# A3000_8MB_Glue.net
KiCad netlist of a schematic drawn in Altium Designer
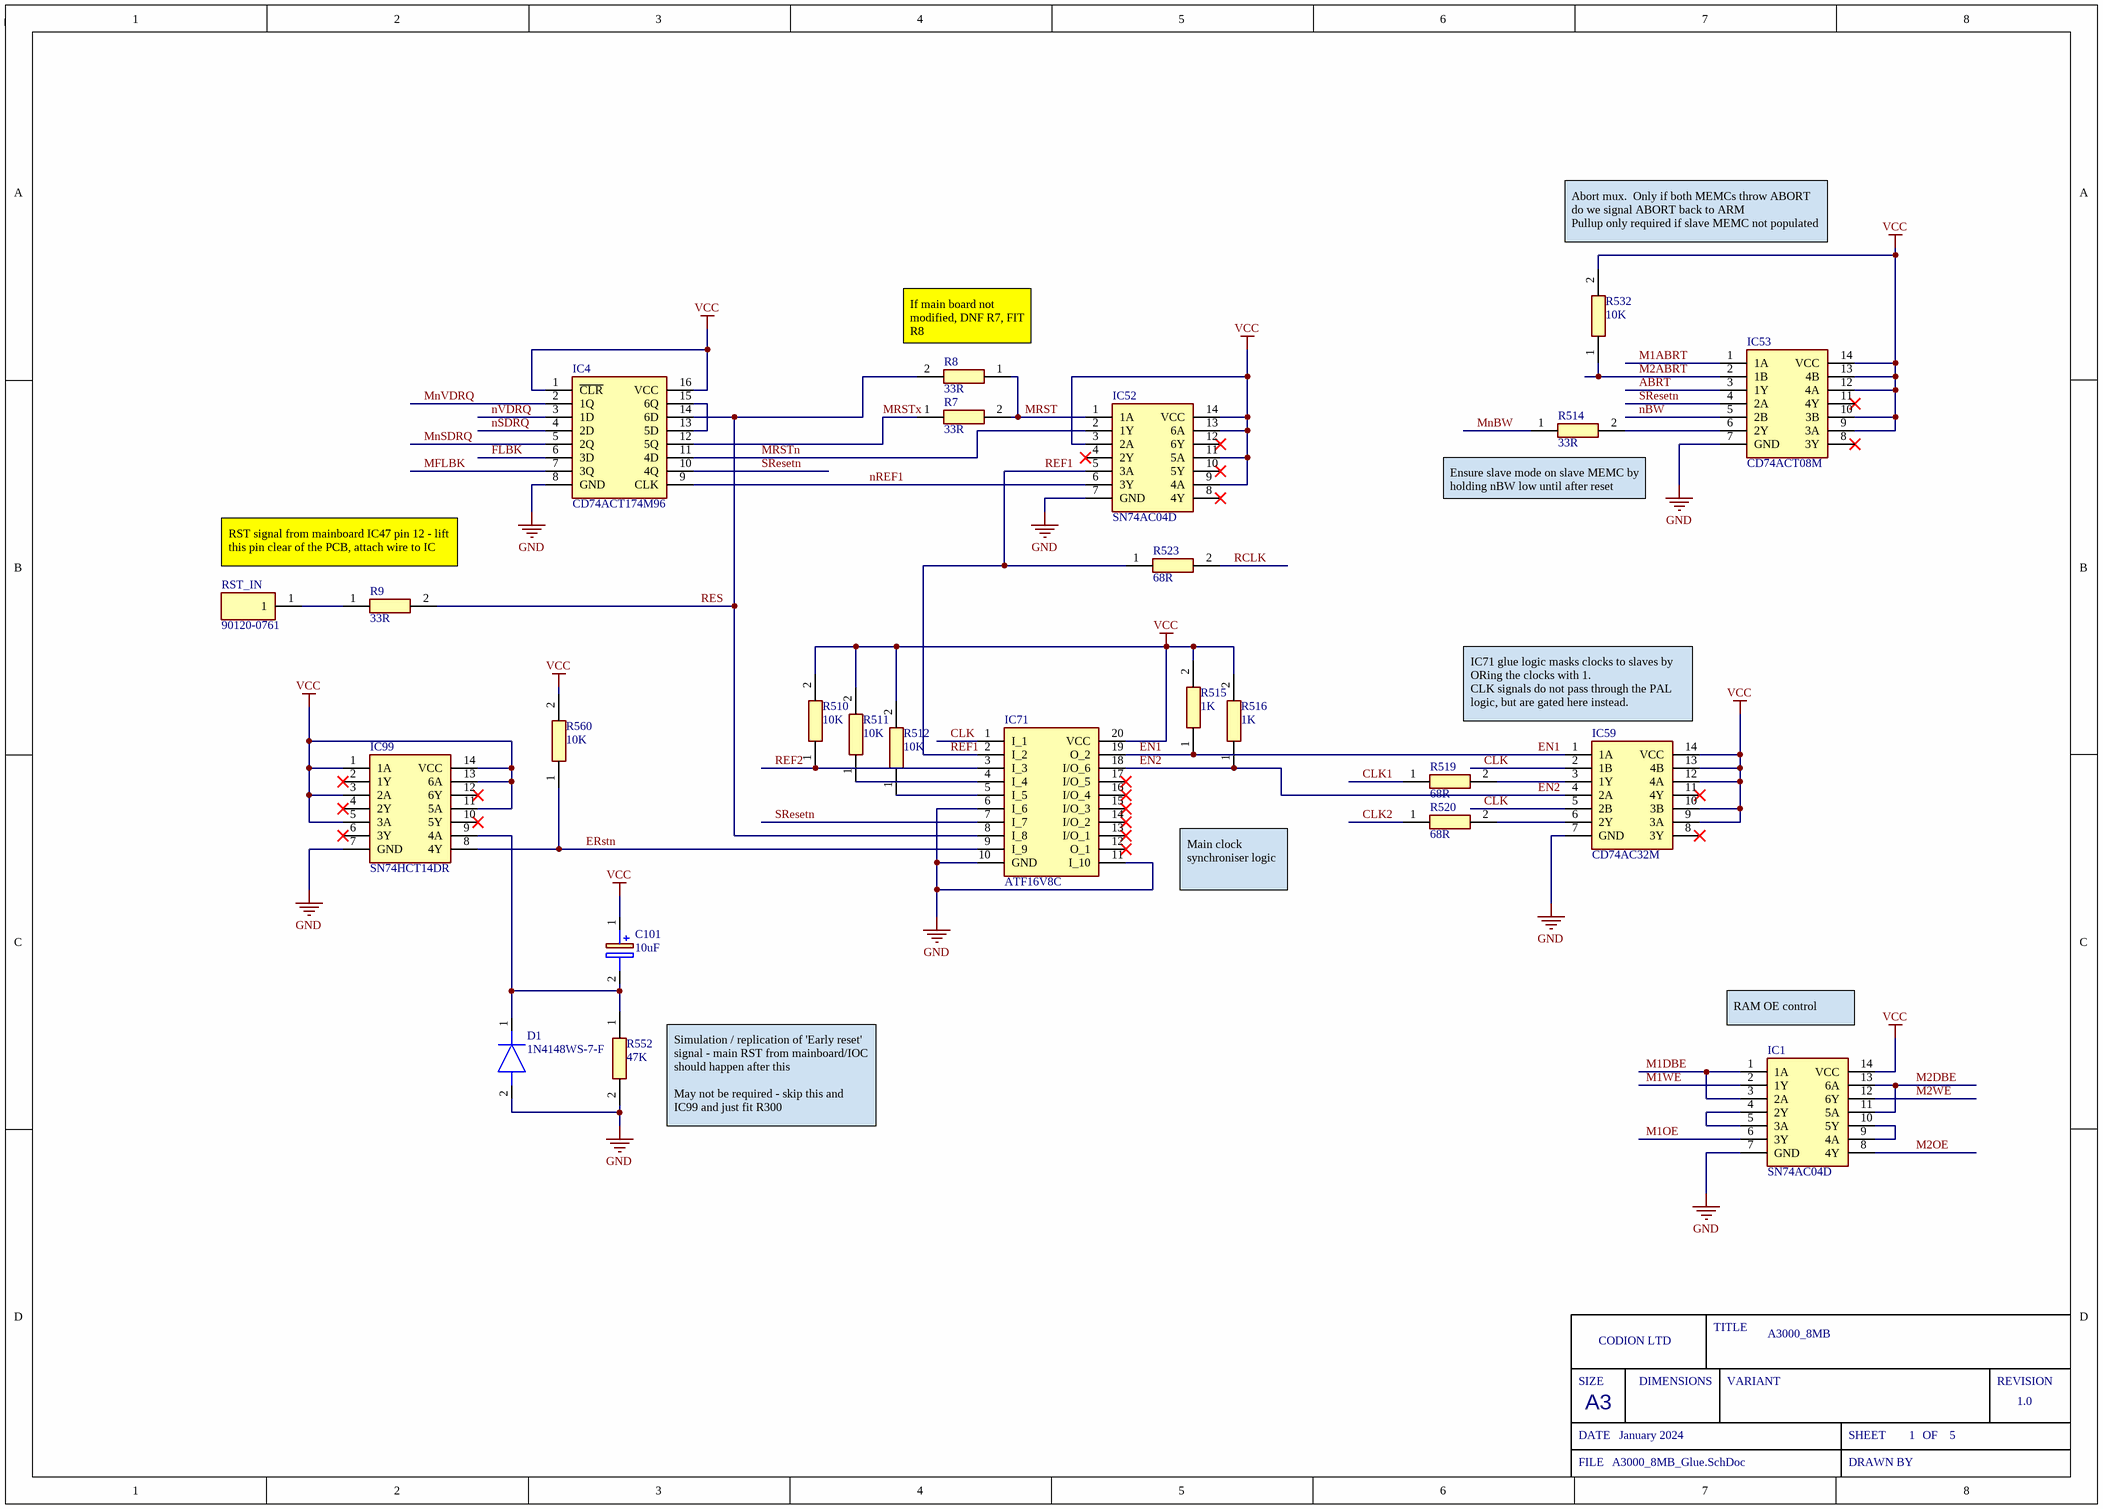
[diagram p0: A3000_8MB_Glue.SchDoc]

(export (version "E")
  (design (tool "Eeschema 10.0.6"))
  (components
    (comp (ref "C101")
      (value "10uF")
      (footprint "SamacSys:EEE0GA101SR")
      (description "Capacitor Polarised")
      (fields
        (field (name "MANUFACTURER_PART_NUMBER") "EEE-1EA100SR")
        (field (name "MOUSER PART NUMBER") "667-EEE-1EA100SR")
      )
      (libsource (lib "*") (part "EEE-1EA100SR"))
    )
    (comp (ref "D1")
      (value "1N4148WS-7-F")
      (footprint "SamacSys:SOD2513X120N")
      (description "Diode")
      (fields (field (name "MOUSER PART NUMBER") "621-1N4148WS-F") (field (name "LCSC PART #") "C2128"))
      (libsource (lib "SamacSys") (part "1N4148WS-7-F"))
    )
    (comp (ref "IC1")
      (value "SN74AC04D")
      (footprint "SamacSys:SOIC127P600X175-14N")
      (description "Integrated Circuit")
      (fields (field (name "MOUSER PART NUMBER") "595-SN74AC04D") (field (name "LCSC PART #") "C352940"))
      (libsource (lib "SamacSys") (part "SN74AC04D"))
    )
    (comp (ref "IC4")
      (value "CD74ACT174M96")
      (footprint "SamacSys:SOIC127P600X175-16N")
      (description "Integrated Circuit")
      (fields (field (name "MOUSER PART NUMBER") "595-CD74ACT174M96"))
      (libsource (lib "*") (part "CD74ACT174M96"))
    )
    (comp (ref "IC52")
      (value "SN74AC04D")
      (footprint "SamacSys:SOIC127P600X175-14N")
      (description "Integrated Circuit")
      (fields (field (name "MOUSER PART NUMBER") "595-SN74AC04D") (field (name "LCSC PART #") "C352940"))
      (libsource (lib "SamacSys") (part "SN74AC04D"))
    )
    (comp (ref "IC53")
      (value "CD74ACT08M")
      (footprint "SamacSys:SOIC127P600X175-14N")
      (description "Integrated Circuit")
      (fields (field (name "MOUSER PART NUMBER") "595-CD74ACT08M") (field (name "LCSC PART #") "C233452"))
      (libsource (lib "*") (part "CD74ACT08M"))
    )
    (comp (ref "IC59")
      (value "CD74AC32M")
      (footprint "SamacSys:SOIC127P600X175-14N")
      (description "Integrated Circuit")
      (fields (field (name "MOUSER PART NUMBER") "595-CD74AC32M") (field (name "LCSC PART #") "C352943"))
      (libsource (lib "SamacSys") (part "CD74AC32M"))
    )
    (comp (ref "IC71")
      (value "ATF16V8C")
      (footprint "SamacSys:DIP762W66P254L2692H508Q20N")
      (description "Integrated Circuit")
      (fields
        (field (name "MANUFACTURER_PART_NUMBER") "PAL16R4AMJ")
        (field (name "MOUSER PART NUMBER") "595-PAL16R4AMJ")
      )
      (libsource (lib "*") (part "PAL16R4AMJ"))
    )
    (comp (ref "IC99")
      (value "SN74HCT14DR")
      (footprint "SamacSys:SOIC127P600X175-14N")
      (description "Integrated Circuit")
      (fields (field (name "MOUSER PART NUMBER") "595-SN74HCT14DR") (field (name "LCSC PART #") "C6769"))
      (libsource (lib "SamacSys") (part "SN74HCT14DR"))
    )
    (comp (ref "R7")
      (value "33R")
      (footprint "SamacSys:RESC1005X40N")
      (description "Resistor")
      (fields
        (field (name "MANUFACTURER_PART_NUMBER") "CRCW040233R0FKED")
        (field (name "MOUSER PART NUMBER") "71-CRCW0402-33-E3")
      )
      (libsource (lib "SamacSys") (part "CRCW040233R0FKED"))
    )
    (comp (ref "R8")
      (value "33R")
      (footprint "SamacSys:RESC1005X40N")
      (description "Resistor")
      (fields
        (field (name "MANUFACTURER_PART_NUMBER") "CRCW040233R0FKED")
        (field (name "MOUSER PART NUMBER") "71-CRCW0402-33-E3")
      )
      (libsource (lib "") (part "CRCW040233R0FKED_1"))
    )
    (comp (ref "R9")
      (value "33R")
      (footprint "SamacSys:RESC1005X40N")
      (description "Resistor")
      (fields
        (field (name "MANUFACTURER_PART_NUMBER") "CRCW040233R0FKED")
        (field (name "MOUSER PART NUMBER") "71-CRCW0402-33-E3")
      )
      (libsource (lib "SamacSys") (part "CRCW040233R0FKED"))
    )
    (comp (ref "R510")
      (value "10K")
      (footprint "SamacSys:RESC1005X40N")
      (description "Resistor")
      (fields
        (field (name "MANUFACTURER_PART_NUMBER") "CRCW040210K0FKEDHP")
        (field (name "MOUSER PART NUMBER") "71-CRCW040210K0FKEDH")
      )
      (libsource (lib "SamacSys") (part "CRCW040210K0FKEDHP"))
    )
    (comp (ref "R511")
      (value "10K")
      (footprint "SamacSys:RESC1005X40N")
      (description "Resistor")
      (fields
        (field (name "MANUFACTURER_PART_NUMBER") "CRCW040210K0FKEDHP")
        (field (name "MOUSER PART NUMBER") "71-CRCW040210K0FKEDH")
      )
      (libsource (lib "SamacSys") (part "CRCW040210K0FKEDHP"))
    )
    (comp (ref "R512")
      (value "10K")
      (footprint "SamacSys:RESC1005X40N")
      (description "Resistor")
      (fields
        (field (name "MANUFACTURER_PART_NUMBER") "CRCW040210K0FKEDHP")
        (field (name "MOUSER PART NUMBER") "71-CRCW040210K0FKEDH")
      )
      (libsource (lib "SamacSys") (part "CRCW040210K0FKEDHP"))
    )
    (comp (ref "R514")
      (value "33R")
      (footprint "SamacSys:RESC1005X40N")
      (description "Resistor")
      (fields
        (field (name "MANUFACTURER_PART_NUMBER") "CRCW040233R0FKED")
        (field (name "MOUSER PART NUMBER") "71-CRCW0402-33-E3")
      )
      (libsource (lib "SamacSys") (part "CRCW040233R0FKED"))
    )
    (comp (ref "R515")
      (value "1K")
      (footprint "SamacSys:RESC1005X40N")
      (description "Resistor")
      (fields
        (field (name "MANUFACTURER_PART_NUMBER") "CRCW04021K00JNED")
        (field (name "MOUSER PART NUMBER") "71-CRCW0402J-1.0K-E3")
      )
      (libsource (lib "SamacSys") (part "CRCW04021K00JNED"))
    )
    (comp (ref "R516")
      (value "1K")
      (footprint "SamacSys:RESC1005X40N")
      (description "Resistor")
      (fields
        (field (name "MANUFACTURER_PART_NUMBER") "CRCW04021K00JNED")
        (field (name "MOUSER PART NUMBER") "71-CRCW0402J-1.0K-E3")
      )
      (libsource (lib "SamacSys") (part "CRCW04021K00JNED"))
    )
    (comp (ref "R519")
      (value "68R")
      (footprint "SamacSys:RESC1005X40N")
      (description "Resistor")
      (fields
        (field (name "MANUFACTURER_PART_NUMBER") "CRCW040268R0FKEDHP")
        (field (name "MOUSER PART NUMBER") "71-CRCW040268R0FKEDH")
      )
      (libsource (lib "SamacSys") (part "CRCW040268R0FKEDHP"))
    )
    (comp (ref "R520")
      (value "68R")
      (footprint "SamacSys:RESC1005X40N")
      (description "Resistor")
      (fields
        (field (name "MANUFACTURER_PART_NUMBER") "CRCW040268R0FKEDHP")
        (field (name "MOUSER PART NUMBER") "71-CRCW040268R0FKEDH")
      )
      (libsource (lib "SamacSys") (part "CRCW040268R0FKEDHP"))
    )
    (comp (ref "R523")
      (value "68R")
      (footprint "SamacSys:RESC1005X40N")
      (description "Resistor")
      (fields
        (field (name "MANUFACTURER_PART_NUMBER") "CRCW040268R0FKEDHP")
        (field (name "MOUSER PART NUMBER") "71-CRCW040268R0FKEDH")
      )
      (libsource (lib "SamacSys") (part "CRCW040268R0FKEDHP"))
    )
    (comp (ref "R532")
      (value "10K")
      (footprint "SamacSys:RESC1005X40N")
      (description "Resistor")
      (fields
        (field (name "MANUFACTURER_PART_NUMBER") "CRCW040210K0FKEDHP")
        (field (name "MOUSER PART NUMBER") "71-CRCW040210K0FKEDH")
      )
      (libsource (lib "SamacSys") (part "CRCW040210K0FKEDHP"))
    )
    (comp (ref "R552")
      (value "47K")
      (footprint "SamacSys:RESC1005X40N")
      (description "Resistor")
      (fields
        (field (name "MANUFACTURER_PART_NUMBER") "CRCW040247K0FKED")
        (field (name "MOUSER PART NUMBER") "71-CRCW0402-47K-E3")
      )
      (libsource (lib "SamacSys") (part "CRCW040247K0FKED"))
    )
    (comp (ref "R560")
      (value "10K")
      (footprint "SamacSys:RESC1005X40N")
      (description "Resistor")
      (fields
        (field (name "MANUFACTURER_PART_NUMBER") "CRCW040210K0FKEDHP")
        (field (name "MOUSER PART NUMBER") "71-CRCW040210K0FKEDH")
      )
      (libsource (lib "SamacSys") (part "CRCW040210K0FKEDHP"))
    )
    (comp (ref "RST_IN")
      (value "90120-0761")
      (footprint "SamacSys:HDRV1W90P0X254_1X1_232X249X560P")
      (description "Connector")
      (fields (field (name "MOUSER PART NUMBER") "538-90120-0761"))
      (libsource (lib "*") (part "90120-0761"))
    )
  )
  (nets
    (net (code "1") (name "/ABRT") (class "Default")
      (node (ref "IC53") (pin "3") (pinfunction "1Y_3") (pintype "passive"))
    )
    (net (code "2") (name "/CLK") (class "Default")
      (node (ref "IC59") (pin "2") (pinfunction "1B_2") (pintype "passive"))
      (node (ref "IC59") (pin "5") (pinfunction "2B_5") (pintype "passive"))
      (node (ref "IC71") (pin "1") (pinfunction "I_1_1") (pintype "passive"))
    )
    (net (code "3") (name "/CLK1") (class "Default")
      (node (ref "R519") (pin "1") (pinfunction "1_1") (pintype "passive"))
    )
    (net (code "4") (name "/CLK2") (class "Default")
      (node (ref "R520") (pin "1") (pinfunction "1_1") (pintype "passive"))
    )
    (net (code "5") (name "/EN1") (class "Default")
      (node (ref "IC59") (pin "1") (pinfunction "1A_1") (pintype "passive"))
      (node (ref "IC71") (pin "19") (pinfunction "O_2_19") (pintype "passive"))
      (node (ref "R515") (pin "1") (pinfunction "1_1") (pintype "passive"))
    )
    (net (code "6") (name "/EN2") (class "Default")
      (node (ref "IC59") (pin "4") (pinfunction "2A_4") (pintype "passive"))
      (node (ref "IC71") (pin "18") (pinfunction "I/O_6_18") (pintype "passive"))
      (node (ref "R516") (pin "1") (pinfunction "1_1") (pintype "passive"))
    )
    (net (code "7") (name "/ERstn") (class "Default")
      (node (ref "IC71") (pin "9") (pinfunction "I_9_9") (pintype "passive"))
      (node (ref "IC99") (pin "8") (pinfunction "4Y_8") (pintype "passive"))
      (node (ref "R560") (pin "1") (pinfunction "1_1") (pintype "passive"))
    )
    (net (code "8") (name "/FLBK") (class "Default")
      (node (ref "IC4") (pin "6") (pinfunction "3D_6") (pintype "passive"))
    )
    (net (code "9") (name "/M1ABRT") (class "Default")
      (node (ref "IC53") (pin "1") (pinfunction "1A_1") (pintype "passive"))
    )
    (net (code "10") (name "/M1DBE") (class "Default")
      (node (ref "IC1") (pin "1") (pinfunction "1A_1") (pintype "passive"))
      (node (ref "IC1") (pin "3") (pinfunction "2A_3") (pintype "passive"))
    )
    (net (code "11") (name "/M1OE") (class "Default")
      (node (ref "IC1") (pin "6") (pinfunction "3Y_6") (pintype "passive"))
    )
    (net (code "12") (name "/M1WE") (class "Default")
      (node (ref "IC1") (pin "2") (pinfunction "1Y_2") (pintype "passive"))
    )
    (net (code "13") (name "/M2ABRT") (class "Default")
      (node (ref "IC53") (pin "2") (pinfunction "1B_2") (pintype "passive"))
      (node (ref "R532") (pin "1") (pinfunction "1_1") (pintype "passive"))
    )
    (net (code "14") (name "/M2DBE") (class "Default")
      (node (ref "IC1") (pin "11") (pinfunction "5A_11") (pintype "passive"))
      (node (ref "IC1") (pin "13") (pinfunction "6A_13") (pintype "passive"))
    )
    (net (code "15") (name "/M2OE") (class "Default")
      (node (ref "IC1") (pin "8") (pinfunction "4Y_8") (pintype "passive"))
    )
    (net (code "16") (name "/M2WE") (class "Default")
      (node (ref "IC1") (pin "12") (pinfunction "6Y_12") (pintype "passive"))
    )
    (net (code "17") (name "/MFLBK") (class "Default")
      (node (ref "IC4") (pin "7") (pinfunction "3Q_7") (pintype "passive"))
    )
    (net (code "18") (name "/MRST") (class "Default")
      (node (ref "IC52") (pin "1") (pinfunction "1A_1") (pintype "passive"))
      (node (ref "R7") (pin "2") (pinfunction "2_2") (pintype "passive"))
      (node (ref "R8") (pin "1") (pinfunction "1_1") (pintype "passive"))
    )
    (net (code "19") (name "/MRSTn") (class "Default")
      (node (ref "IC4") (pin "11") (pinfunction "4D_11") (pintype "passive"))
      (node (ref "IC52") (pin "2") (pinfunction "1Y_2") (pintype "passive"))
    )
    (net (code "20") (name "/MRSTx") (class "Default")
      (node (ref "IC4") (pin "12") (pinfunction "5Q_12") (pintype "passive"))
      (node (ref "R7") (pin "1") (pinfunction "1_1") (pintype "passive"))
    )
    (net (code "21") (name "/MnBW") (class "Default")
      (node (ref "R514") (pin "1") (pinfunction "1_1") (pintype "passive"))
    )
    (net (code "22") (name "/MnSDRQ") (class "Default")
      (node (ref "IC4") (pin "5") (pinfunction "2Q_5") (pintype "passive"))
    )
    (net (code "23") (name "/MnVDRQ") (class "Default")
      (node (ref "IC4") (pin "2") (pinfunction "1Q_2") (pintype "passive"))
    )
    (net (code "24") (name "/RCLK") (class "Default")
      (node (ref "R523") (pin "2") (pinfunction "2_2") (pintype "passive"))
    )
    (net (code "25") (name "/REF1") (class "Default")
      (node (ref "IC52") (pin "5") (pinfunction "3A_5") (pintype "passive"))
      (node (ref "IC71") (pin "2") (pinfunction "I_2_2") (pintype "passive"))
      (node (ref "R523") (pin "1") (pinfunction "1_1") (pintype "passive"))
    )
    (net (code "26") (name "/REF2") (class "Default")
      (node (ref "IC71") (pin "3") (pinfunction "I_3_3") (pintype "passive"))
      (node (ref "R510") (pin "1") (pinfunction "1_1") (pintype "passive"))
    )
    (net (code "27") (name "/RES") (class "Default")
      (node (ref "IC4") (pin "14") (pinfunction "6D_14") (pintype "passive"))
      (node (ref "IC71") (pin "8") (pinfunction "I_8_8") (pintype "passive"))
      (node (ref "R8") (pin "2") (pinfunction "2_2") (pintype "passive"))
      (node (ref "R9") (pin "2") (pinfunction "2_2") (pintype "passive"))
    )
    (net (code "28") (name "/SResetn") (class "Default")
      (node (ref "IC4") (pin "10") (pinfunction "4Q_10") (pintype "passive"))
      (node (ref "IC53") (pin "4") (pinfunction "2A_4") (pintype "passive"))
      (node (ref "IC71") (pin "7") (pinfunction "I_7_7") (pintype "passive"))
    )
    (net (code "29") (name "/nBW") (class "Default")
      (node (ref "IC53") (pin "5") (pinfunction "2B_5") (pintype "passive"))
    )
    (net (code "30") (name "/nREF1") (class "Default")
      (node (ref "IC4") (pin "9") (pinfunction "CLK_9") (pintype "passive"))
      (node (ref "IC52") (pin "6") (pinfunction "3Y_6") (pintype "passive"))
    )
    (net (code "31") (name "/nSDRQ") (class "Default")
      (node (ref "IC4") (pin "4") (pinfunction "2D_4") (pintype "passive"))
    )
    (net (code "32") (name "/nVDRQ") (class "Default")
      (node (ref "IC4") (pin "3") (pinfunction "1D_3") (pintype "passive"))
    )
    (net (code "33") (name "GND") (class "Default")
      (node (ref "D1") (pin "2") (pinfunction "A_2") (pintype "passive"))
      (node (ref "IC1") (pin "7") (pinfunction "GND_7") (pintype "passive"))
      (node (ref "IC4") (pin "8") (pinfunction "GND_8") (pintype "passive"))
      (node (ref "IC52") (pin "7") (pinfunction "GND_7") (pintype "passive"))
      (node (ref "IC53") (pin "7") (pinfunction "GND_7") (pintype "passive"))
      (node (ref "IC59") (pin "7") (pinfunction "GND_7") (pintype "passive"))
      (node (ref "IC71") (pin "10") (pinfunction "GND_10") (pintype "passive"))
      (node (ref "IC71") (pin "11") (pinfunction "I_10_11") (pintype "passive"))
      (node (ref "IC71") (pin "6") (pinfunction "I_6_6") (pintype "passive"))
      (node (ref "IC99") (pin "7") (pinfunction "GND_7") (pintype "passive"))
      (node (ref "R552") (pin "2") (pinfunction "2_2") (pintype "passive"))
    )
    (net (code "34") (name "Net-(C101--)") (class "Default")
      (node (ref "C101") (pin "2") (pinfunction "-_2") (pintype "passive"))
      (node (ref "D1") (pin "1") (pinfunction "K_1") (pintype "passive"))
      (node (ref "IC99") (pin "9") (pinfunction "4A_9") (pintype "passive"))
      (node (ref "R552") (pin "1") (pinfunction "1_1") (pintype "passive"))
    )
    (net (code "35") (name "Net-(IC1-2Y)") (class "Default")
      (node (ref "IC1") (pin "4") (pinfunction "2Y_4") (pintype "passive"))
      (node (ref "IC1") (pin "5") (pinfunction "3A_5") (pintype "passive"))
    )
    (net (code "36") (name "Net-(IC1-4A)") (class "Default")
      (node (ref "IC1") (pin "10") (pinfunction "5Y_10") (pintype "passive"))
      (node (ref "IC1") (pin "9") (pinfunction "4A_9") (pintype "passive"))
    )
    (net (code "37") (name "Net-(IC4-5D)") (class "Default")
      (node (ref "IC4") (pin "13") (pinfunction "5D_13") (pintype "passive"))
      (node (ref "IC4") (pin "15") (pinfunction "6Q_15") (pintype "passive"))
    )
    (net (code "38") (name "Net-(IC53-2Y)") (class "Default")
      (node (ref "IC53") (pin "6") (pinfunction "2Y_6") (pintype "passive"))
      (node (ref "R514") (pin "2") (pinfunction "2_2") (pintype "passive"))
    )
    (net (code "39") (name "Net-(IC59-1Y)") (class "Default")
      (node (ref "IC59") (pin "3") (pinfunction "1Y_3") (pintype "passive"))
      (node (ref "R519") (pin "2") (pinfunction "2_2") (pintype "passive"))
    )
    (net (code "40") (name "Net-(IC59-2Y)") (class "Default")
      (node (ref "IC59") (pin "6") (pinfunction "2Y_6") (pintype "passive"))
      (node (ref "R520") (pin "2") (pinfunction "2_2") (pintype "passive"))
    )
    (net (code "41") (name "Net-(IC71-I_4)") (class "Default")
      (node (ref "IC71") (pin "4") (pinfunction "I_4_4") (pintype "passive"))
      (node (ref "R511") (pin "1") (pinfunction "1_1") (pintype "passive"))
    )
    (net (code "42") (name "Net-(IC71-I_5)") (class "Default")
      (node (ref "IC71") (pin "5") (pinfunction "I_5_5") (pintype "passive"))
      (node (ref "R512") (pin "1") (pinfunction "1_1") (pintype "passive"))
    )
    (net (code "43") (name "Net-(R9-Pad1)") (class "Default")
      (node (ref "R9") (pin "1") (pinfunction "1_1") (pintype "passive"))
      (node (ref "RST_IN") (pin "1") (pinfunction "1_1") (pintype "passive"))
    )
    (net (code "44") (name "VCC") (class "Default")
      (node (ref "C101") (pin "1") (pinfunction "+_1") (pintype "passive"))
      (node (ref "IC1") (pin "14") (pinfunction "VCC_14") (pintype "passive"))
      (node (ref "IC4") (pin "1") (pinfunction "~{CLR}_1") (pintype "passive"))
      (node (ref "IC4") (pin "16") (pinfunction "VCC_16") (pintype "passive"))
      (node (ref "IC52") (pin "11") (pinfunction "5A_11") (pintype "passive"))
      (node (ref "IC52") (pin "13") (pinfunction "6A_13") (pintype "passive"))
      (node (ref "IC52") (pin "14") (pinfunction "VCC_14") (pintype "passive"))
      (node (ref "IC52") (pin "3") (pinfunction "2A_3") (pintype "passive"))
      (node (ref "IC52") (pin "9") (pinfunction "4A_9") (pintype "passive"))
      (node (ref "IC53") (pin "10") (pinfunction "3B_10") (pintype "passive"))
      (node (ref "IC53") (pin "12") (pinfunction "4A_12") (pintype "passive"))
      (node (ref "IC53") (pin "13") (pinfunction "4B_13") (pintype "passive"))
      (node (ref "IC53") (pin "14") (pinfunction "VCC_14") (pintype "passive"))
      (node (ref "IC53") (pin "9") (pinfunction "3A_9") (pintype "passive"))
      (node (ref "IC59") (pin "10") (pinfunction "3B_10") (pintype "passive"))
      (node (ref "IC59") (pin "12") (pinfunction "4A_12") (pintype "passive"))
      (node (ref "IC59") (pin "13") (pinfunction "4B_13") (pintype "passive"))
      (node (ref "IC59") (pin "14") (pinfunction "VCC_14") (pintype "passive"))
      (node (ref "IC59") (pin "9") (pinfunction "3A_9") (pintype "passive"))
      (node (ref "IC71") (pin "20") (pinfunction "VCC_20") (pintype "passive"))
      (node (ref "IC99") (pin "1") (pinfunction "1A_1") (pintype "passive"))
      (node (ref "IC99") (pin "11") (pinfunction "5A_11") (pintype "passive"))
      (node (ref "IC99") (pin "13") (pinfunction "6A_13") (pintype "passive"))
      (node (ref "IC99") (pin "14") (pinfunction "VCC_14") (pintype "passive"))
      (node (ref "IC99") (pin "3") (pinfunction "2A_3") (pintype "passive"))
      (node (ref "IC99") (pin "5") (pinfunction "3A_5") (pintype "passive"))
      (node (ref "R510") (pin "2") (pinfunction "2_2") (pintype "passive"))
      (node (ref "R511") (pin "2") (pinfunction "2_2") (pintype "passive"))
      (node (ref "R512") (pin "2") (pinfunction "2_2") (pintype "passive"))
      (node (ref "R515") (pin "2") (pinfunction "2_2") (pintype "passive"))
      (node (ref "R516") (pin "2") (pinfunction "2_2") (pintype "passive"))
      (node (ref "R532") (pin "2") (pinfunction "2_2") (pintype "passive"))
      (node (ref "R560") (pin "2") (pinfunction "2_2") (pintype "passive"))
    )
    (net (code "45") (name "unconnected-(IC52-2Y-Pad4)") (class "Default")
      (node (ref "IC52") (pin "4") (pinfunction "2Y_4") (pintype "passive+no_connect"))
    )
    (net (code "46") (name "unconnected-(IC52-4Y-Pad8)") (class "Default")
      (node (ref "IC52") (pin "8") (pinfunction "4Y_8") (pintype "passive+no_connect"))
    )
    (net (code "47") (name "unconnected-(IC52-5Y-Pad10)") (class "Default")
      (node (ref "IC52") (pin "10") (pinfunction "5Y_10") (pintype "passive+no_connect"))
    )
    (net (code "48") (name "unconnected-(IC52-6Y-Pad12)") (class "Default")
      (node (ref "IC52") (pin "12") (pinfunction "6Y_12") (pintype "passive+no_connect"))
    )
    (net (code "49") (name "unconnected-(IC53-3Y-Pad8)") (class "Default")
      (node (ref "IC53") (pin "8") (pinfunction "3Y_8") (pintype "passive+no_connect"))
    )
    (net (code "50") (name "unconnected-(IC53-4Y-Pad11)") (class "Default")
      (node (ref "IC53") (pin "11") (pinfunction "4Y_11") (pintype "passive+no_connect"))
    )
    (net (code "51") (name "unconnected-(IC59-3Y-Pad8)") (class "Default")
      (node (ref "IC59") (pin "8") (pinfunction "3Y_8") (pintype "passive+no_connect"))
    )
    (net (code "52") (name "unconnected-(IC59-4Y-Pad11)") (class "Default")
      (node (ref "IC59") (pin "11") (pinfunction "4Y_11") (pintype "passive+no_connect"))
    )
    (net (code "53") (name "unconnected-(IC71-I{slash}O_1-Pad13)") (class "Default")
      (node (ref "IC71") (pin "13") (pinfunction "I/O_1_13") (pintype "passive+no_connect"))
    )
    (net (code "54") (name "unconnected-(IC71-I{slash}O_2-Pad14)") (class "Default")
      (node (ref "IC71") (pin "14") (pinfunction "I/O_2_14") (pintype "passive+no_connect"))
    )
    (net (code "55") (name "unconnected-(IC71-I{slash}O_3-Pad15)") (class "Default")
      (node (ref "IC71") (pin "15") (pinfunction "I/O_3_15") (pintype "passive+no_connect"))
    )
    (net (code "56") (name "unconnected-(IC71-I{slash}O_4-Pad16)") (class "Default")
      (node (ref "IC71") (pin "16") (pinfunction "I/O_4_16") (pintype "passive+no_connect"))
    )
    (net (code "57") (name "unconnected-(IC71-I{slash}O_5-Pad17)") (class "Default")
      (node (ref "IC71") (pin "17") (pinfunction "I/O_5_17") (pintype "passive+no_connect"))
    )
    (net (code "58") (name "unconnected-(IC71-O_1-Pad12)") (class "Default")
      (node (ref "IC71") (pin "12") (pinfunction "O_1_12") (pintype "passive+no_connect"))
    )
    (net (code "59") (name "unconnected-(IC99-1Y-Pad2)") (class "Default")
      (node (ref "IC99") (pin "2") (pinfunction "1Y_2") (pintype "passive+no_connect"))
    )
    (net (code "60") (name "unconnected-(IC99-2Y-Pad4)") (class "Default")
      (node (ref "IC99") (pin "4") (pinfunction "2Y_4") (pintype "passive+no_connect"))
    )
    (net (code "61") (name "unconnected-(IC99-3Y-Pad6)") (class "Default")
      (node (ref "IC99") (pin "6") (pinfunction "3Y_6") (pintype "passive+no_connect"))
    )
    (net (code "62") (name "unconnected-(IC99-5Y-Pad10)") (class "Default")
      (node (ref "IC99") (pin "10") (pinfunction "5Y_10") (pintype "passive+no_connect"))
    )
    (net (code "63") (name "unconnected-(IC99-6Y-Pad12)") (class "Default")
      (node (ref "IC99") (pin "12") (pinfunction "6Y_12") (pintype "passive+no_connect"))
    )
  )
)
